# Connector-side-1.net
KiCad netlist of a schematic drawn in Altium Designer
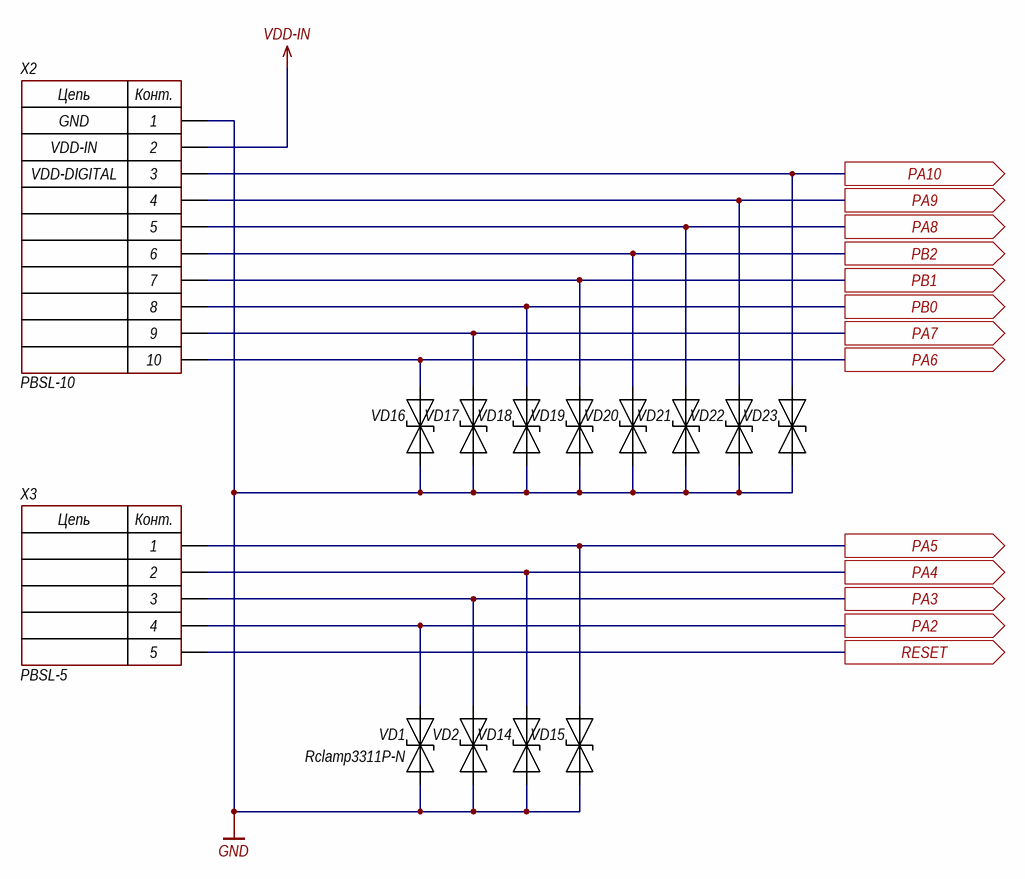
[diagram p0: Connector-side-1.SchDoc]

(export (version "E")
  (design (tool "Eeschema 10.0.6"))
  (components
    (comp (ref "VD1")
      (value "Rclamp3311P-N")
      (footprint "DFN1006-2")
      (fields (field (name "MANUFACTURER") "BORN"))
      (libsource (lib "Diods") (part "TVS-diod"))
    )
    (comp (ref "VD2")
      (value "Rclamp3311P-N")
      (footprint "DFN1006-2")
      (fields (field (name "MANUFACTURER") "BORN"))
      (libsource (lib "Diods") (part "TVS-diod"))
    )
    (comp (ref "VD14")
      (value "Rclamp3311P-N")
      (footprint "DFN1006-2")
      (fields (field (name "MANUFACTURER") "BORN"))
      (libsource (lib "Diods") (part "TVS-diod"))
    )
    (comp (ref "VD15")
      (value "Rclamp3311P-N")
      (footprint "DFN1006-2")
      (fields (field (name "MANUFACTURER") "BORN"))
      (libsource (lib "Diods") (part "TVS-diod"))
    )
    (comp (ref "VD16")
      (value "Rclamp3311P-N")
      (footprint "DFN1006-2")
      (fields (field (name "MANUFACTURER") "BORN"))
      (libsource (lib "Diods") (part "TVS-diod"))
    )
    (comp (ref "VD17")
      (value "Rclamp3311P-N")
      (footprint "DFN1006-2")
      (fields (field (name "MANUFACTURER") "BORN"))
      (libsource (lib "Diods") (part "TVS-diod"))
    )
    (comp (ref "VD18")
      (value "Rclamp3311P-N")
      (footprint "DFN1006-2")
      (fields (field (name "MANUFACTURER") "BORN"))
      (libsource (lib "Diods") (part "TVS-diod"))
    )
    (comp (ref "VD19")
      (value "Rclamp3311P-N")
      (footprint "DFN1006-2")
      (fields (field (name "MANUFACTURER") "BORN"))
      (libsource (lib "Diods") (part "TVS-diod"))
    )
    (comp (ref "VD20")
      (value "Rclamp3311P-N")
      (footprint "DFN1006-2")
      (fields (field (name "MANUFACTURER") "BORN"))
      (libsource (lib "Diods") (part "TVS-diod"))
    )
    (comp (ref "VD21")
      (value "Rclamp3311P-N")
      (footprint "DFN1006-2")
      (fields (field (name "MANUFACTURER") "BORN"))
      (libsource (lib "Diods") (part "TVS-diod"))
    )
    (comp (ref "VD22")
      (value "Rclamp3311P-N")
      (footprint "DFN1006-2")
      (fields (field (name "MANUFACTURER") "BORN"))
      (libsource (lib "Diods") (part "TVS-diod"))
    )
    (comp (ref "VD23")
      (value "Rclamp3311P-N")
      (footprint "DFN1006-2")
      (fields (field (name "MANUFACTURER") "BORN"))
      (libsource (lib "Diods") (part "TVS-diod"))
    )
    (comp (ref "X2")
      (value "PBSL-10")
      (footprint "CON: PBSL-10")
      (libsource (lib "Connectors") (part "10-Connector"))
    )
    (comp (ref "X3")
      (value "PBSL-5")
      (footprint "CON: PBSL-5")
      (libsource (lib "Connectors") (part "5-Connector"))
    )
  )
  (nets
    (net (code "1") (name "/PA2") (class "Default")
      (node (ref "VD1") (pin "2") (pinfunction "C_2") (pintype "passive"))
      (node (ref "X3") (pin "4") (pinfunction "4_4") (pintype "passive"))
    )
    (net (code "2") (name "/PA3") (class "Default")
      (node (ref "VD2") (pin "2") (pinfunction "C_2") (pintype "passive"))
      (node (ref "X3") (pin "3") (pinfunction "3_3") (pintype "passive"))
    )
    (net (code "3") (name "/PA4") (class "Default")
      (node (ref "VD14") (pin "2") (pinfunction "C_2") (pintype "passive"))
      (node (ref "X3") (pin "2") (pinfunction "2_2") (pintype "passive"))
    )
    (net (code "4") (name "/PA5") (class "Default")
      (node (ref "VD15") (pin "2") (pinfunction "C_2") (pintype "passive"))
      (node (ref "X3") (pin "1") (pinfunction "1_1") (pintype "passive"))
    )
    (net (code "5") (name "/PA6") (class "Default")
      (node (ref "VD16") (pin "2") (pinfunction "C_2") (pintype "passive"))
      (node (ref "X2") (pin "10") (pinfunction "10_10") (pintype "passive"))
    )
    (net (code "6") (name "/PA7") (class "Default")
      (node (ref "VD17") (pin "2") (pinfunction "C_2") (pintype "passive"))
      (node (ref "X2") (pin "9") (pinfunction "9_9") (pintype "passive"))
    )
    (net (code "7") (name "/PA8") (class "Default")
      (node (ref "VD21") (pin "2") (pinfunction "C_2") (pintype "passive"))
      (node (ref "X2") (pin "5") (pinfunction "5_5") (pintype "passive"))
    )
    (net (code "8") (name "/PA9") (class "Default")
      (node (ref "VD22") (pin "2") (pinfunction "C_2") (pintype "passive"))
      (node (ref "X2") (pin "4") (pinfunction "4_4") (pintype "passive"))
    )
    (net (code "9") (name "/PA10") (class "Default")
      (node (ref "VD23") (pin "2") (pinfunction "C_2") (pintype "passive"))
      (node (ref "X2") (pin "3") (pinfunction "3_3") (pintype "passive"))
    )
    (net (code "10") (name "/PB0") (class "Default")
      (node (ref "VD18") (pin "2") (pinfunction "C_2") (pintype "passive"))
      (node (ref "X2") (pin "8") (pinfunction "8_8") (pintype "passive"))
    )
    (net (code "11") (name "/PB1") (class "Default")
      (node (ref "VD19") (pin "2") (pinfunction "C_2") (pintype "passive"))
      (node (ref "X2") (pin "7") (pinfunction "7_7") (pintype "passive"))
    )
    (net (code "12") (name "/PB2") (class "Default")
      (node (ref "VD20") (pin "2") (pinfunction "C_2") (pintype "passive"))
      (node (ref "X2") (pin "6") (pinfunction "6_6") (pintype "passive"))
    )
    (net (code "13") (name "/RESET") (class "Default")
      (node (ref "X3") (pin "5") (pinfunction "5_5") (pintype "passive"))
    )
    (net (code "14") (name "GND") (class "Default")
      (node (ref "VD1") (pin "1") (pinfunction "A_1") (pintype "passive"))
      (node (ref "VD14") (pin "1") (pinfunction "A_1") (pintype "passive"))
      (node (ref "VD15") (pin "1") (pinfunction "A_1") (pintype "passive"))
      (node (ref "VD16") (pin "1") (pinfunction "A_1") (pintype "passive"))
      (node (ref "VD17") (pin "1") (pinfunction "A_1") (pintype "passive"))
      (node (ref "VD18") (pin "1") (pinfunction "A_1") (pintype "passive"))
      (node (ref "VD19") (pin "1") (pinfunction "A_1") (pintype "passive"))
      (node (ref "VD2") (pin "1") (pinfunction "A_1") (pintype "passive"))
      (node (ref "VD20") (pin "1") (pinfunction "A_1") (pintype "passive"))
      (node (ref "VD21") (pin "1") (pinfunction "A_1") (pintype "passive"))
      (node (ref "VD22") (pin "1") (pinfunction "A_1") (pintype "passive"))
      (node (ref "VD23") (pin "1") (pinfunction "A_1") (pintype "passive"))
      (node (ref "X2") (pin "1") (pinfunction "1_1") (pintype "passive"))
    )
    (net (code "15") (name "VDD-IN") (class "Default")
      (node (ref "X2") (pin "2") (pinfunction "2_2") (pintype "passive"))
    )
  )
)
